# sensors.net
KiCad netlist of a schematic drawn in Altium Designer
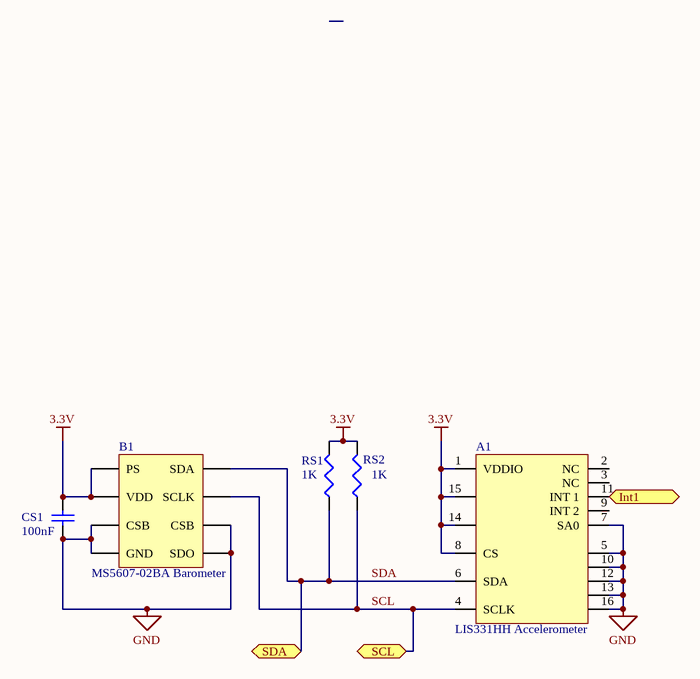
[diagram p0: sensors.SchDoc]

(export (version "E")
  (design (tool "Eeschema 10.0.6"))
  (components
    (comp (ref "A1")
      (value "LIS331HH Accelerometer")
      (footprint "LGA16")
      (libsource (lib "Rocket_Sensors") (part "LIS331HH Accelerometer"))
    )
    (comp (ref "B1")
      (value "MS5607-02BA Barometer")
      (footprint "Barometer LCC")
      (libsource (lib "Rocket_Sensors") (part "MS5607-02BA Barometer"))
    )
    (comp (ref "CS1")
      (value "100nF")
      (footprint "C1206")
      (description "Capacitor (Semiconductor SIM Model)")
      (fields (field (name "Comment") "Cap Semi") (field (name "PUBLISHER") "Altium Limited"))
      (libsource (lib "Miscellaneous Devices") (part "Cap Semi"))
    )
    (comp (ref "RS1")
      (value "1K")
      (footprint "J1-0603")
      (description "Resistor")
      (fields (field (name "Comment") "Res3") (field (name "PUBLISHER") "Altium Limited"))
      (libsource (lib "Miscellaneous Devices") (part "Res3"))
    )
    (comp (ref "RS2")
      (value "1K")
      (footprint "J1-0603")
      (description "Resistor")
      (fields (field (name "Comment") "Res3") (field (name "PUBLISHER") "Altium Limited"))
      (libsource (lib "Miscellaneous Devices") (part "Res3"))
    )
  )
  (nets
    (net (code "1") (name "/Int1") (class "Default")
      (node (ref "A1") (pin "11") (pinfunction "INT_1_11") (pintype "passive"))
    )
    (net (code "2") (name "/SCL") (class "Default")
      (node (ref "A1") (pin "4") (pinfunction "SCLK_4") (pintype "passive"))
      (node (ref "B1") (pin "8") (pinfunction "SCLK_8") (pintype "passive"))
      (node (ref "RS2") (pin "1") (pinfunction "1_1") (pintype "passive"))
    )
    (net (code "3") (name "/SDA") (class "Default")
      (node (ref "A1") (pin "6") (pinfunction "SDA_6") (pintype "passive"))
      (node (ref "B1") (pin "7") (pinfunction "SDA_7") (pintype "passive"))
      (node (ref "RS1") (pin "1") (pinfunction "1_1") (pintype "passive"))
    )
    (net (code "4") (name "3.3V") (class "Default")
      (node (ref "A1") (pin "1") (pinfunction "VDDIO_1") (pintype "passive"))
      (node (ref "A1") (pin "14") (pintype "passive"))
      (node (ref "A1") (pin "15") (pintype "passive"))
      (node (ref "A1") (pin "8") (pinfunction "CS_8") (pintype "passive"))
      (node (ref "B1") (pin "1") (pinfunction "VDD_1") (pintype "passive"))
      (node (ref "B1") (pin "2") (pinfunction "PS_2") (pintype "passive"))
      (node (ref "CS1") (pin "2") (pinfunction "2_2") (pintype "passive"))
      (node (ref "RS1") (pin "2") (pinfunction "2_2") (pintype "passive"))
      (node (ref "RS2") (pin "2") (pinfunction "2_2") (pintype "passive"))
    )
    (net (code "5") (name "GND") (class "Default")
      (node (ref "A1") (pin "10") (pinfunction "10_10") (pintype "passive"))
      (node (ref "A1") (pin "12") (pintype "passive"))
      (node (ref "A1") (pin "13") (pintype "passive"))
      (node (ref "A1") (pin "16") (pintype "passive"))
      (node (ref "A1") (pin "5") (pinfunction "GND_5") (pintype "passive"))
      (node (ref "A1") (pin "7") (pinfunction "SA0_7") (pintype "passive"))
      (node (ref "B1") (pin "3") (pinfunction "GND_3") (pintype "passive"))
      (node (ref "B1") (pin "4") (pinfunction "CSB_4") (pintype "passive"))
      (node (ref "B1") (pin "5") (pinfunction "CSB_5") (pintype "passive"))
      (node (ref "B1") (pin "6") (pinfunction "SDO_6") (pintype "passive"))
      (node (ref "CS1") (pin "1") (pinfunction "1_1") (pintype "passive"))
    )
    (net (code "6") (name "unconnected-(A1-INT_2-Pad9)") (class "Default")
      (node (ref "A1") (pin "9") (pinfunction "INT_2_9") (pintype "passive"))
    )
    (net (code "7") (name "unconnected-(A1-NC-Pad2)") (class "Default")
      (node (ref "A1") (pin "2") (pinfunction "NC_2") (pintype "passive"))
    )
    (net (code "8") (name "unconnected-(A1-NC-Pad3)") (class "Default")
      (node (ref "A1") (pin "3") (pinfunction "NC_3") (pintype "passive"))
    )
  )
)
